# Connectors.net
KiCad netlist of a schematic drawn in Altium Designer
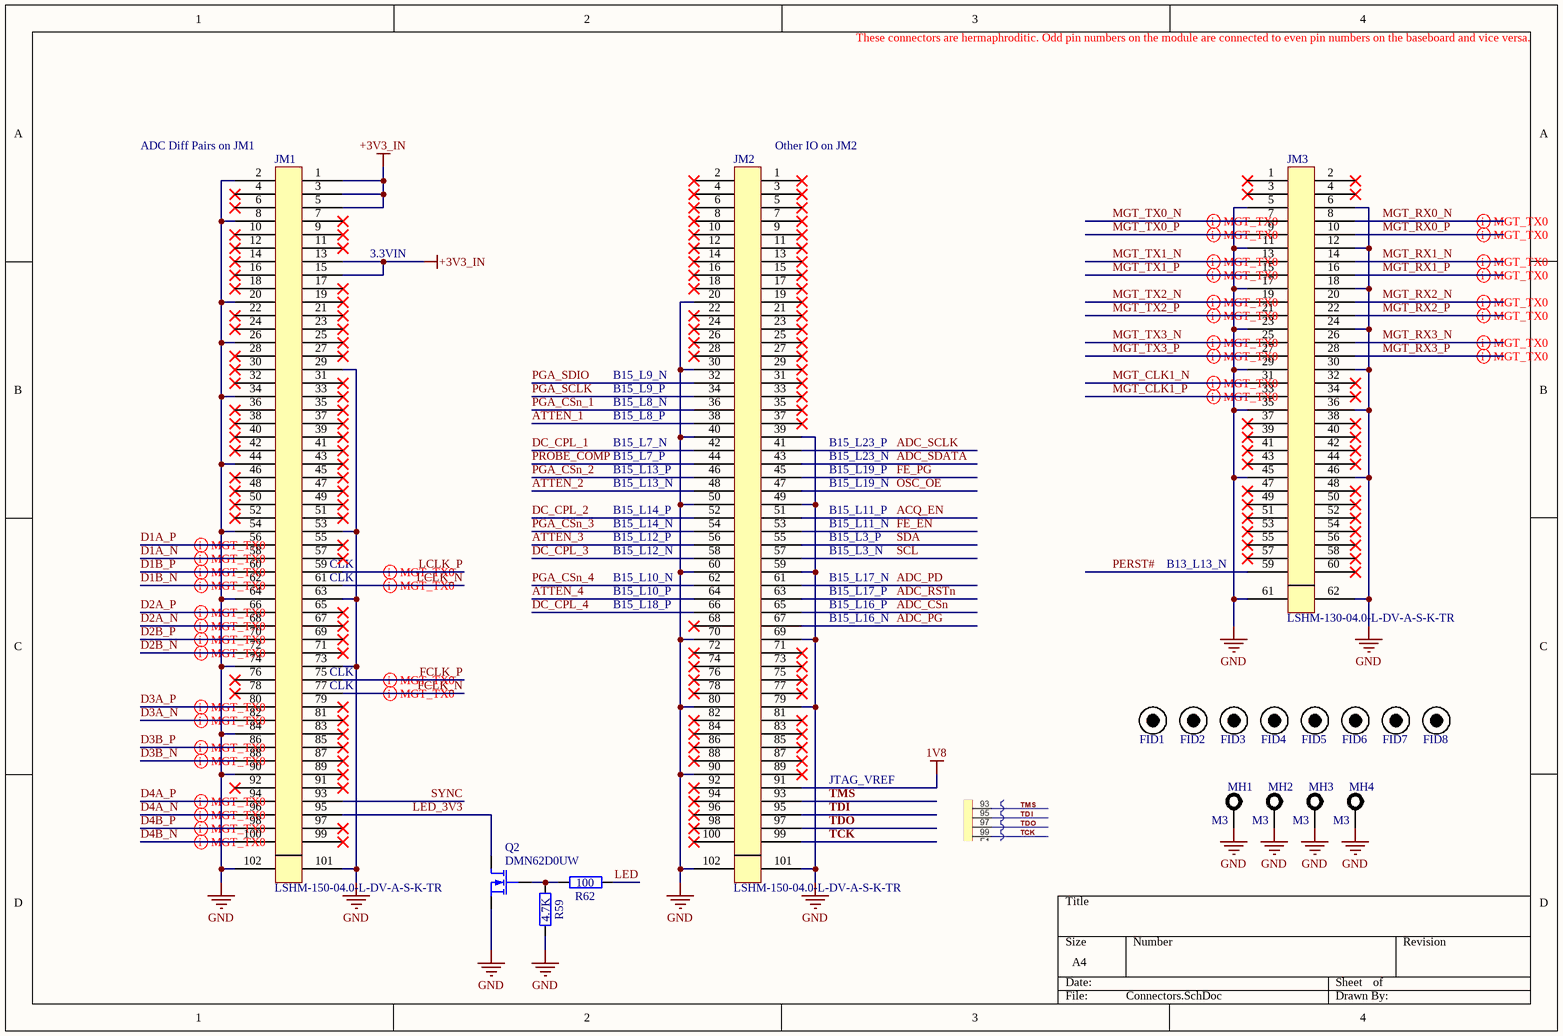
[diagram p0: Connectors.SchDoc]

(export (version "E")
  (design (tool "Eeschema 10.0.6"))
  (components
    (comp (ref "FID1") (value "PCB") (footprint "GEN_FID") (libsource (lib "DSO") (part "FID 1mm")))
    (comp (ref "FID2") (value "PCB") (footprint "GEN_FID") (libsource (lib "DSO") (part "FID 1mm")))
    (comp (ref "FID3") (value "PCB") (footprint "GEN_FID") (libsource (lib "DSO") (part "FID 1mm")))
    (comp (ref "FID4") (value "PCB") (footprint "GEN_FID") (libsource (lib "DSO") (part "FID 1mm")))
    (comp (ref "FID5") (value "PCB") (footprint "GEN_FID") (libsource (lib "DSO") (part "FID 1mm")))
    (comp (ref "FID6") (value "PCB") (footprint "GEN_FID") (libsource (lib "DSO") (part "FID 1mm")))
    (comp (ref "FID7") (value "PCB") (footprint "GEN_FID") (libsource (lib "DSO") (part "FID 1mm")))
    (comp (ref "FID8") (value "PCB") (footprint "GEN_FID") (libsource (lib "DSO") (part "FID 1mm")))
    (comp (ref "JM1")
      (value "LSHM-150-04.0-L-DV-A-S-K-TR")
      (footprint "SAM_LSHM-150-XX.X-XX-DV-A-S")
      (libsource (lib "DSO") (part "CONN LSHM-150-04.0-L-DV-A-S-K-TR"))
    )
    (comp (ref "JM2")
      (value "LSHM-150-04.0-L-DV-A-S-K-TR")
      (footprint "SAM_LSHM-150-XX.X-XX-DV-A-S")
      (libsource (lib "DSO") (part "CONN LSHM-150-04.0-L-DV-A-S-K-TR"))
    )
    (comp (ref "JM3")
      (value "LSHM-130-04.0-L-DV-A-S-K-TR")
      (footprint "SAM_LSHM-130-XX.X-XX-DV-A-S")
      (libsource (lib "DSO") (part "CONN LSHM-130-04.0-L-DV-A-S-K-TR"))
    )
    (comp (ref "MH1") (value "M3") (footprint "MH M3") (libsource (lib "DSO") (part "MH M3")))
    (comp (ref "MH2") (value "M3") (footprint "MH M3") (libsource (lib "DSO") (part "MH M3")))
    (comp (ref "MH3") (value "M3") (footprint "MH M3") (libsource (lib "DSO") (part "MH M3")))
    (comp (ref "MH4") (value "M3") (footprint "MH M3") (libsource (lib "DSO") (part "MH M3")))
    (comp (ref "Q2")
      (value "DMN62D0UW")
      (footprint "GEN_SOT_323")
      (libsource (lib "DSO") (part "NMOS DMN62D0UW"))
    )
    (comp (ref "R59")
      (value "4.7K")
      (footprint "GEN_R_0201")
      (fields (field (name "TOLERANCE") "1%"))
      (libsource (lib "DSO") (part "RES 4.7K OHM 1% 1/20W 0201"))
    )
    (comp (ref "R62")
      (value "100")
      (footprint "GEN_R_0201")
      (fields (field (name "TOLERANCE") "1%"))
      (libsource (lib "DSO") (part "RES 100 OHM 1% 1/20W 0201"))
    )
  )
  (nets
    (net (code "1") (name "+3V3_IN") (class "Default")
      (node (ref "JM1") (pin "1") (pinfunction "1_1") (pintype "passive"))
      (node (ref "JM1") (pin "13") (pinfunction "13_13") (pintype "passive"))
      (node (ref "JM1") (pin "15") (pinfunction "15_15") (pintype "passive"))
      (node (ref "JM1") (pin "3") (pinfunction "3_3") (pintype "passive"))
      (node (ref "JM1") (pin "5") (pinfunction "5_5") (pintype "passive"))
    )
    (net (code "2") (name "/ACQ_EN") (class "Default")
      (node (ref "JM2") (pin "51") (pinfunction "51_51") (pintype "passive"))
    )
    (net (code "3") (name "/ADC_CSn") (class "Default")
      (node (ref "JM2") (pin "65") (pinfunction "65_65") (pintype "passive"))
    )
    (net (code "4") (name "/ADC_PD") (class "Default")
      (node (ref "JM2") (pin "61") (pinfunction "61_61") (pintype "passive"))
    )
    (net (code "5") (name "/ADC_PG") (class "Default")
      (node (ref "JM2") (pin "67") (pinfunction "67_67") (pintype "passive"))
    )
    (net (code "6") (name "/ADC_RSTn") (class "Default")
      (node (ref "JM2") (pin "63") (pinfunction "63_63") (pintype "passive"))
    )
    (net (code "7") (name "/ADC_SCLK") (class "Default")
      (node (ref "JM2") (pin "41") (pinfunction "41_41") (pintype "passive"))
    )
    (net (code "8") (name "/ADC_SDATA") (class "Default")
      (node (ref "JM2") (pin "43") (pinfunction "43_43") (pintype "passive"))
    )
    (net (code "9") (name "/ATTEN_1") (class "Default")
      (node (ref "JM2") (pin "38") (pinfunction "38_38") (pintype "passive"))
    )
    (net (code "10") (name "/ATTEN_2") (class "Default")
      (node (ref "JM2") (pin "48") (pinfunction "48_48") (pintype "passive"))
    )
    (net (code "11") (name "/ATTEN_3") (class "Default")
      (node (ref "JM2") (pin "56") (pinfunction "56_56") (pintype "passive"))
    )
    (net (code "12") (name "/ATTEN_4") (class "Default")
      (node (ref "JM2") (pin "64") (pinfunction "64_64") (pintype "passive"))
    )
    (net (code "13") (name "/D1A_N") (class "Default")
      (node (ref "JM1") (pin "58") (pinfunction "58_58") (pintype "passive"))
    )
    (net (code "14") (name "/D1A_P") (class "Default")
      (node (ref "JM1") (pin "56") (pinfunction "56_56") (pintype "passive"))
    )
    (net (code "15") (name "/D1B_N") (class "Default")
      (node (ref "JM1") (pin "62") (pinfunction "62_62") (pintype "passive"))
    )
    (net (code "16") (name "/D1B_P") (class "Default")
      (node (ref "JM1") (pin "60") (pinfunction "60_60") (pintype "passive"))
    )
    (net (code "17") (name "/D2A_N") (class "Default")
      (node (ref "JM1") (pin "68") (pinfunction "68_68") (pintype "passive"))
    )
    (net (code "18") (name "/D2A_P") (class "Default")
      (node (ref "JM1") (pin "66") (pinfunction "66_66") (pintype "passive"))
    )
    (net (code "19") (name "/D2B_N") (class "Default")
      (node (ref "JM1") (pin "72") (pinfunction "72_72") (pintype "passive"))
    )
    (net (code "20") (name "/D2B_P") (class "Default")
      (node (ref "JM1") (pin "70") (pinfunction "70_70") (pintype "passive"))
    )
    (net (code "21") (name "/D3A_N") (class "Default")
      (node (ref "JM1") (pin "82") (pinfunction "82_82") (pintype "passive"))
    )
    (net (code "22") (name "/D3A_P") (class "Default")
      (node (ref "JM1") (pin "80") (pinfunction "80_80") (pintype "passive"))
    )
    (net (code "23") (name "/D3B_N") (class "Default")
      (node (ref "JM1") (pin "88") (pinfunction "88_88") (pintype "passive"))
    )
    (net (code "24") (name "/D3B_P") (class "Default")
      (node (ref "JM1") (pin "86") (pinfunction "86_86") (pintype "passive"))
    )
    (net (code "25") (name "/D4A_N") (class "Default")
      (node (ref "JM1") (pin "96") (pinfunction "96_96") (pintype "passive"))
    )
    (net (code "26") (name "/D4A_P") (class "Default")
      (node (ref "JM1") (pin "94") (pinfunction "94_94") (pintype "passive"))
    )
    (net (code "27") (name "/D4B_N") (class "Default")
      (node (ref "JM1") (pin "100") (pinfunction "100_100") (pintype "passive"))
    )
    (net (code "28") (name "/D4B_P") (class "Default")
      (node (ref "JM1") (pin "98") (pinfunction "98_98") (pintype "passive"))
    )
    (net (code "29") (name "/DC_CPL_1") (class "Default")
      (node (ref "JM2") (pin "42") (pinfunction "42_42") (pintype "passive"))
    )
    (net (code "30") (name "/DC_CPL_2") (class "Default")
      (node (ref "JM2") (pin "52") (pinfunction "52_52") (pintype "passive"))
    )
    (net (code "31") (name "/DC_CPL_3") (class "Default")
      (node (ref "JM2") (pin "58") (pinfunction "58_58") (pintype "passive"))
    )
    (net (code "32") (name "/DC_CPL_4") (class "Default")
      (node (ref "JM2") (pin "66") (pinfunction "66_66") (pintype "passive"))
    )
    (net (code "33") (name "/FCLK_N") (class "Default")
      (node (ref "JM1") (pin "77") (pinfunction "77_77") (pintype "passive"))
    )
    (net (code "34") (name "/FCLK_P") (class "Default")
      (node (ref "JM1") (pin "75") (pinfunction "75_75") (pintype "passive"))
    )
    (net (code "35") (name "/FE_EN") (class "Default")
      (node (ref "JM2") (pin "53") (pinfunction "53_53") (pintype "passive"))
    )
    (net (code "36") (name "/FE_PG") (class "Default")
      (node (ref "JM2") (pin "45") (pinfunction "45_45") (pintype "passive"))
    )
    (net (code "37") (name "/LCLK_N") (class "Default")
      (node (ref "JM1") (pin "61") (pinfunction "61_61") (pintype "passive"))
    )
    (net (code "38") (name "/LCLK_P") (class "Default")
      (node (ref "JM1") (pin "59") (pinfunction "59_59") (pintype "passive"))
    )
    (net (code "39") (name "/LED") (class "Default")
      (node (ref "R62") (pin "1") (pinfunction "1_1") (pintype "passive"))
    )
    (net (code "40") (name "/LED_3V3") (class "Default")
      (node (ref "JM1") (pin "95") (pinfunction "95_95") (pintype "passive"))
      (node (ref "Q2") (pin "1") (pinfunction "D_1") (pintype "passive"))
    )
    (net (code "41") (name "/MGT_CLK1_N") (class "Default")
      (node (ref "JM3") (pin "31") (pinfunction "31_31") (pintype "passive"))
    )
    (net (code "42") (name "/MGT_CLK1_P") (class "Default")
      (node (ref "JM3") (pin "33") (pinfunction "33_33") (pintype "passive"))
    )
    (net (code "43") (name "/MGT_RX0_N") (class "Default")
      (node (ref "JM3") (pin "8") (pinfunction "8_8") (pintype "passive"))
    )
    (net (code "44") (name "/MGT_RX0_P") (class "Default")
      (node (ref "JM3") (pin "10") (pinfunction "10_10") (pintype "passive"))
    )
    (net (code "45") (name "/MGT_RX1_N") (class "Default")
      (node (ref "JM3") (pin "14") (pinfunction "14_14") (pintype "passive"))
    )
    (net (code "46") (name "/MGT_RX1_P") (class "Default")
      (node (ref "JM3") (pin "16") (pinfunction "16_16") (pintype "passive"))
    )
    (net (code "47") (name "/MGT_RX2_N") (class "Default")
      (node (ref "JM3") (pin "20") (pinfunction "20_20") (pintype "passive"))
    )
    (net (code "48") (name "/MGT_RX2_P") (class "Default")
      (node (ref "JM3") (pin "22") (pinfunction "22_22") (pintype "passive"))
    )
    (net (code "49") (name "/MGT_RX3_N") (class "Default")
      (node (ref "JM3") (pin "26") (pinfunction "26_26") (pintype "passive"))
    )
    (net (code "50") (name "/MGT_RX3_P") (class "Default")
      (node (ref "JM3") (pin "28") (pinfunction "28_28") (pintype "passive"))
    )
    (net (code "51") (name "/MGT_TX0_N") (class "Default")
      (node (ref "JM3") (pin "7") (pinfunction "7_7") (pintype "passive"))
    )
    (net (code "52") (name "/MGT_TX0_P") (class "Default")
      (node (ref "JM3") (pin "9") (pinfunction "9_9") (pintype "passive"))
    )
    (net (code "53") (name "/MGT_TX1_N") (class "Default")
      (node (ref "JM3") (pin "13") (pinfunction "13_13") (pintype "passive"))
    )
    (net (code "54") (name "/MGT_TX1_P") (class "Default")
      (node (ref "JM3") (pin "15") (pinfunction "15_15") (pintype "passive"))
    )
    (net (code "55") (name "/MGT_TX2_N") (class "Default")
      (node (ref "JM3") (pin "19") (pinfunction "19_19") (pintype "passive"))
    )
    (net (code "56") (name "/MGT_TX2_P") (class "Default")
      (node (ref "JM3") (pin "21") (pinfunction "21_21") (pintype "passive"))
    )
    (net (code "57") (name "/MGT_TX3_N") (class "Default")
      (node (ref "JM3") (pin "25") (pinfunction "25_25") (pintype "passive"))
    )
    (net (code "58") (name "/MGT_TX3_P") (class "Default")
      (node (ref "JM3") (pin "27") (pinfunction "27_27") (pintype "passive"))
    )
    (net (code "59") (name "/OSC_OE") (class "Default")
      (node (ref "JM2") (pin "47") (pinfunction "47_47") (pintype "passive"))
    )
    (net (code "60") (name "/PERST#") (class "Default")
      (node (ref "JM3") (pin "59") (pinfunction "59_59") (pintype "passive"))
    )
    (net (code "61") (name "/PGA_CSn_1") (class "Default")
      (node (ref "JM2") (pin "36") (pinfunction "36_36") (pintype "passive"))
    )
    (net (code "62") (name "/PGA_CSn_2") (class "Default")
      (node (ref "JM2") (pin "46") (pinfunction "46_46") (pintype "passive"))
    )
    (net (code "63") (name "/PGA_CSn_3") (class "Default")
      (node (ref "JM2") (pin "54") (pinfunction "54_54") (pintype "passive"))
    )
    (net (code "64") (name "/PGA_CSn_4") (class "Default")
      (node (ref "JM2") (pin "62") (pinfunction "62_62") (pintype "passive"))
    )
    (net (code "65") (name "/PGA_SCLK") (class "Default")
      (node (ref "JM2") (pin "34") (pinfunction "34_34") (pintype "passive"))
    )
    (net (code "66") (name "/PGA_SDIO") (class "Default")
      (node (ref "JM2") (pin "32") (pinfunction "32_32") (pintype "passive"))
    )
    (net (code "67") (name "/PROBE_COMP") (class "Default")
      (node (ref "JM2") (pin "44") (pinfunction "44_44") (pintype "passive"))
    )
    (net (code "68") (name "/SCL") (class "Default")
      (node (ref "JM2") (pin "57") (pinfunction "57_57") (pintype "passive"))
    )
    (net (code "69") (name "/SDA") (class "Default")
      (node (ref "JM2") (pin "55") (pinfunction "55_55") (pintype "passive"))
    )
    (net (code "70") (name "/SYNC") (class "Default")
      (node (ref "JM1") (pin "93") (pinfunction "93_93") (pintype "passive"))
    )
    (net (code "71") (name "/TCK") (class "Default")
      (node (ref "JM2") (pin "99") (pinfunction "99_99") (pintype "passive"))
    )
    (net (code "72") (name "/TDI") (class "Default")
      (node (ref "JM2") (pin "95") (pinfunction "95_95") (pintype "passive"))
    )
    (net (code "73") (name "/TDO") (class "Default")
      (node (ref "JM2") (pin "97") (pinfunction "97_97") (pintype "passive"))
    )
    (net (code "74") (name "/TMS") (class "Default")
      (node (ref "JM2") (pin "93") (pinfunction "93_93") (pintype "passive"))
    )
    (net (code "75") (name "1V8") (class "Default")
      (node (ref "JM2") (pin "91") (pinfunction "91_91") (pintype "passive"))
    )
    (net (code "76") (name "GND") (class "Default")
      (node (ref "JM1") (pin "101") (pinfunction "101_101") (pintype "passive"))
      (node (ref "JM1") (pin "102") (pinfunction "102_102") (pintype "passive"))
      (node (ref "JM1") (pin "2") (pinfunction "2_2") (pintype "passive"))
      (node (ref "JM1") (pin "20") (pinfunction "20_20") (pintype "passive"))
      (node (ref "JM1") (pin "26") (pinfunction "26_26") (pintype "passive"))
      (node (ref "JM1") (pin "29") (pinfunction "29_29") (pintype "passive"))
      (node (ref "JM1") (pin "34") (pinfunction "34_34") (pintype "passive"))
      (node (ref "JM1") (pin "44") (pinfunction "44_44") (pintype "passive"))
      (node (ref "JM1") (pin "53") (pinfunction "53_53") (pintype "passive"))
      (node (ref "JM1") (pin "54") (pinfunction "54_54") (pintype "passive"))
      (node (ref "JM1") (pin "63") (pinfunction "63_63") (pintype "passive"))
      (node (ref "JM1") (pin "64") (pinfunction "64_64") (pintype "passive"))
      (node (ref "JM1") (pin "73") (pinfunction "73_73") (pintype "passive"))
      (node (ref "JM1") (pin "74") (pinfunction "74_74") (pintype "passive"))
      (node (ref "JM1") (pin "8") (pinfunction "8_8") (pintype "passive"))
      (node (ref "JM1") (pin "84") (pinfunction "84_84") (pintype "passive"))
      (node (ref "JM1") (pin "90") (pinfunction "90_90") (pintype "passive"))
      (node (ref "JM2") (pin "101") (pinfunction "101_101") (pintype "passive"))
      (node (ref "JM2") (pin "102") (pinfunction "102_102") (pintype "passive"))
      (node (ref "JM2") (pin "20") (pinfunction "20_20") (pintype "passive"))
      (node (ref "JM2") (pin "30") (pinfunction "30_30") (pintype "passive"))
      (node (ref "JM2") (pin "39") (pinfunction "39_39") (pintype "passive"))
      (node (ref "JM2") (pin "40") (pinfunction "40_40") (pintype "passive"))
      (node (ref "JM2") (pin "49") (pinfunction "49_49") (pintype "passive"))
      (node (ref "JM2") (pin "50") (pinfunction "50_50") (pintype "passive"))
      (node (ref "JM2") (pin "59") (pinfunction "59_59") (pintype "passive"))
      (node (ref "JM2") (pin "60") (pinfunction "60_60") (pintype "passive"))
      (node (ref "JM2") (pin "69") (pinfunction "69_69") (pintype "passive"))
      (node (ref "JM2") (pin "70") (pinfunction "70_70") (pintype "passive"))
      (node (ref "JM2") (pin "79") (pinfunction "79_79") (pintype "passive"))
      (node (ref "JM2") (pin "80") (pinfunction "80_80") (pintype "passive"))
      (node (ref "JM2") (pin "90") (pinfunction "90_90") (pintype "passive"))
      (node (ref "JM3") (pin "11") (pinfunction "11_11") (pintype "passive"))
      (node (ref "JM3") (pin "12") (pinfunction "12_12") (pintype "passive"))
      (node (ref "JM3") (pin "17") (pinfunction "17_17") (pintype "passive"))
      (node (ref "JM3") (pin "18") (pinfunction "18_18") (pintype "passive"))
      (node (ref "JM3") (pin "23") (pinfunction "23_23") (pintype "passive"))
      (node (ref "JM3") (pin "24") (pinfunction "24_24") (pintype "passive"))
      (node (ref "JM3") (pin "29") (pinfunction "29_29") (pintype "passive"))
      (node (ref "JM3") (pin "30") (pinfunction "30_30") (pintype "passive"))
      (node (ref "JM3") (pin "35") (pinfunction "35_35") (pintype "passive"))
      (node (ref "JM3") (pin "36") (pinfunction "36_36") (pintype "passive"))
      (node (ref "JM3") (pin "45") (pinfunction "45_45") (pintype "passive"))
      (node (ref "JM3") (pin "46") (pinfunction "46_46") (pintype "passive"))
      (node (ref "JM3") (pin "5") (pinfunction "5_5") (pintype "passive"))
      (node (ref "JM3") (pin "6") (pinfunction "6_6") (pintype "passive"))
      (node (ref "JM3") (pin "61") (pinfunction "61_61") (pintype "passive"))
      (node (ref "JM3") (pin "62") (pinfunction "62_62") (pintype "passive"))
      (node (ref "MH1") (pin "1") (pinfunction "1_1") (pintype "passive"))
      (node (ref "MH2") (pin "1") (pinfunction "1_1") (pintype "passive"))
      (node (ref "MH3") (pin "1") (pinfunction "1_1") (pintype "passive"))
      (node (ref "MH4") (pin "1") (pinfunction "1_1") (pintype "passive"))
      (node (ref "Q2") (pin "3") (pinfunction "S_3") (pintype "passive"))
      (node (ref "R59") (pin "2") (pinfunction "2_2") (pintype "passive"))
    )
    (net (code "77") (name "Net-(Q2-G)") (class "Default")
      (node (ref "Q2") (pin "2") (pinfunction "G_2") (pintype "passive"))
      (node (ref "R59") (pin "1") (pinfunction "1_1") (pintype "passive"))
      (node (ref "R62") (pin "2") (pinfunction "2_2") (pintype "passive"))
    )
    (net (code "78") (name "unconnected-(JM1-Pad4)") (class "Default")
      (node (ref "JM1") (pin "4") (pinfunction "4_4") (pintype "passive+no_connect"))
    )
    (net (code "79") (name "unconnected-(JM1-Pad6)") (class "Default")
      (node (ref "JM1") (pin "6") (pinfunction "6_6") (pintype "passive+no_connect"))
    )
    (net (code "80") (name "unconnected-(JM1-Pad7)") (class "Default")
      (node (ref "JM1") (pin "7") (pinfunction "7_7") (pintype "passive+no_connect"))
    )
    (net (code "81") (name "unconnected-(JM1-Pad9)") (class "Default")
      (node (ref "JM1") (pin "9") (pinfunction "9_9") (pintype "passive+no_connect"))
    )
    (net (code "82") (name "unconnected-(JM1-Pad10)") (class "Default")
      (node (ref "JM1") (pin "10") (pinfunction "10_10") (pintype "passive+no_connect"))
    )
    (net (code "83") (name "unconnected-(JM1-Pad11)") (class "Default")
      (node (ref "JM1") (pin "11") (pinfunction "11_11") (pintype "passive+no_connect"))
    )
    (net (code "84") (name "unconnected-(JM1-Pad12)") (class "Default")
      (node (ref "JM1") (pin "12") (pinfunction "12_12") (pintype "passive+no_connect"))
    )
    (net (code "85") (name "unconnected-(JM1-Pad14)") (class "Default")
      (node (ref "JM1") (pin "14") (pinfunction "14_14") (pintype "passive+no_connect"))
    )
    (net (code "86") (name "unconnected-(JM1-Pad16)") (class "Default")
      (node (ref "JM1") (pin "16") (pinfunction "16_16") (pintype "passive+no_connect"))
    )
    (net (code "87") (name "unconnected-(JM1-Pad17)") (class "Default")
      (node (ref "JM1") (pin "17") (pinfunction "17_17") (pintype "passive+no_connect"))
    )
    (net (code "88") (name "unconnected-(JM1-Pad18)") (class "Default")
      (node (ref "JM1") (pin "18") (pinfunction "18_18") (pintype "passive+no_connect"))
    )
    (net (code "89") (name "unconnected-(JM1-Pad19)") (class "Default")
      (node (ref "JM1") (pin "19") (pinfunction "19_19") (pintype "passive+no_connect"))
    )
    (net (code "90") (name "unconnected-(JM1-Pad21)") (class "Default")
      (node (ref "JM1") (pin "21") (pinfunction "21_21") (pintype "passive+no_connect"))
    )
    (net (code "91") (name "unconnected-(JM1-Pad22)") (class "Default")
      (node (ref "JM1") (pin "22") (pinfunction "22_22") (pintype "passive+no_connect"))
    )
    (net (code "92") (name "unconnected-(JM1-Pad23)") (class "Default")
      (node (ref "JM1") (pin "23") (pinfunction "23_23") (pintype "passive+no_connect"))
    )
    (net (code "93") (name "unconnected-(JM1-Pad24)") (class "Default")
      (node (ref "JM1") (pin "24") (pinfunction "24_24") (pintype "passive+no_connect"))
    )
    (net (code "94") (name "unconnected-(JM1-Pad25)") (class "Default")
      (node (ref "JM1") (pin "25") (pinfunction "25_25") (pintype "passive+no_connect"))
    )
    (net (code "95") (name "unconnected-(JM1-Pad27)") (class "Default")
      (node (ref "JM1") (pin "27") (pinfunction "27_27") (pintype "passive+no_connect"))
    )
    (net (code "96") (name "unconnected-(JM1-Pad28)") (class "Default")
      (node (ref "JM1") (pin "28") (pinfunction "28_28") (pintype "passive+no_connect"))
    )
    (net (code "97") (name "unconnected-(JM1-Pad30)") (class "Default")
      (node (ref "JM1") (pin "30") (pinfunction "30_30") (pintype "passive+no_connect"))
    )
    (net (code "98") (name "unconnected-(JM1-Pad31)") (class "Default")
      (node (ref "JM1") (pin "31") (pinfunction "31_31") (pintype "passive+no_connect"))
    )
    (net (code "99") (name "unconnected-(JM1-Pad32)") (class "Default")
      (node (ref "JM1") (pin "32") (pinfunction "32_32") (pintype "passive+no_connect"))
    )
    (net (code "100") (name "unconnected-(JM1-Pad33)") (class "Default")
      (node (ref "JM1") (pin "33") (pinfunction "33_33") (pintype "passive+no_connect"))
    )
    (net (code "101") (name "unconnected-(JM1-Pad35)") (class "Default")
      (node (ref "JM1") (pin "35") (pinfunction "35_35") (pintype "passive+no_connect"))
    )
    (net (code "102") (name "unconnected-(JM1-Pad36)") (class "Default")
      (node (ref "JM1") (pin "36") (pinfunction "36_36") (pintype "passive+no_connect"))
    )
    (net (code "103") (name "unconnected-(JM1-Pad37)") (class "Default")
      (node (ref "JM1") (pin "37") (pinfunction "37_37") (pintype "passive+no_connect"))
    )
    (net (code "104") (name "unconnected-(JM1-Pad38)") (class "Default")
      (node (ref "JM1") (pin "38") (pinfunction "38_38") (pintype "passive+no_connect"))
    )
    (net (code "105") (name "unconnected-(JM1-Pad39)") (class "Default")
      (node (ref "JM1") (pin "39") (pinfunction "39_39") (pintype "passive+no_connect"))
    )
    (net (code "106") (name "unconnected-(JM1-Pad40)") (class "Default")
      (node (ref "JM1") (pin "40") (pinfunction "40_40") (pintype "passive+no_connect"))
    )
    (net (code "107") (name "unconnected-(JM1-Pad41)") (class "Default")
      (node (ref "JM1") (pin "41") (pinfunction "41_41") (pintype "passive+no_connect"))
    )
    (net (code "108") (name "unconnected-(JM1-Pad42)") (class "Default")
      (node (ref "JM1") (pin "42") (pinfunction "42_42") (pintype "passive+no_connect"))
    )
    (net (code "109") (name "unconnected-(JM1-Pad43)") (class "Default")
      (node (ref "JM1") (pin "43") (pinfunction "43_43") (pintype "passive+no_connect"))
    )
    (net (code "110") (name "unconnected-(JM1-Pad45)") (class "Default")
      (node (ref "JM1") (pin "45") (pinfunction "45_45") (pintype "passive+no_connect"))
    )
    (net (code "111") (name "unconnected-(JM1-Pad46)") (class "Default")
      (node (ref "JM1") (pin "46") (pinfunction "46_46") (pintype "passive+no_connect"))
    )
    (net (code "112") (name "unconnected-(JM1-Pad47)") (class "Default")
      (node (ref "JM1") (pin "47") (pinfunction "47_47") (pintype "passive+no_connect"))
    )
    (net (code "113") (name "unconnected-(JM1-Pad48)") (class "Default")
      (node (ref "JM1") (pin "48") (pinfunction "48_48") (pintype "passive+no_connect"))
    )
    (net (code "114") (name "unconnected-(JM1-Pad49)") (class "Default")
      (node (ref "JM1") (pin "49") (pinfunction "49_49") (pintype "passive+no_connect"))
    )
    (net (code "115") (name "unconnected-(JM1-Pad50)") (class "Default")
      (node (ref "JM1") (pin "50") (pinfunction "50_50") (pintype "passive+no_connect"))
    )
    (net (code "116") (name "unconnected-(JM1-Pad51)") (class "Default")
      (node (ref "JM1") (pin "51") (pinfunction "51_51") (pintype "passive+no_connect"))
    )
    (net (code "117") (name "unconnected-(JM1-Pad52)") (class "Default")
      (node (ref "JM1") (pin "52") (pinfunction "52_52") (pintype "passive+no_connect"))
    )
    (net (code "118") (name "unconnected-(JM1-Pad55)") (class "Default")
      (node (ref "JM1") (pin "55") (pinfunction "55_55") (pintype "passive+no_connect"))
    )
    (net (code "119") (name "unconnected-(JM1-Pad57)") (class "Default")
      (node (ref "JM1") (pin "57") (pinfunction "57_57") (pintype "passive+no_connect"))
    )
    (net (code "120") (name "unconnected-(JM1-Pad65)") (class "Default")
      (node (ref "JM1") (pin "65") (pinfunction "65_65") (pintype "passive+no_connect"))
    )
    (net (code "121") (name "unconnected-(JM1-Pad67)") (class "Default")
      (node (ref "JM1") (pin "67") (pinfunction "67_67") (pintype "passive+no_connect"))
    )
    (net (code "122") (name "unconnected-(JM1-Pad69)") (class "Default")
      (node (ref "JM1") (pin "69") (pinfunction "69_69") (pintype "passive+no_connect"))
    )
    (net (code "123") (name "unconnected-(JM1-Pad71)") (class "Default")
      (node (ref "JM1") (pin "71") (pinfunction "71_71") (pintype "passive+no_connect"))
    )
    (net (code "124") (name "unconnected-(JM1-Pad76)") (class "Default")
      (node (ref "JM1") (pin "76") (pinfunction "76_76") (pintype "passive+no_connect"))
    )
    (net (code "125") (name "unconnected-(JM1-Pad78)") (class "Default")
      (node (ref "JM1") (pin "78") (pinfunction "78_78") (pintype "passive+no_connect"))
    )
    (net (code "126") (name "unconnected-(JM1-Pad79)") (class "Default")
      (node (ref "JM1") (pin "79") (pinfunction "79_79") (pintype "passive+no_connect"))
    )
    (net (code "127") (name "unconnected-(JM1-Pad81)") (class "Default")
      (node (ref "JM1") (pin "81") (pinfunction "81_81") (pintype "passive+no_connect"))
    )
    (net (code "128") (name "unconnected-(JM1-Pad83)") (class "Default")
      (node (ref "JM1") (pin "83") (pinfunction "83_83") (pintype "passive+no_connect"))
    )
    (net (code "129") (name "unconnected-(JM1-Pad85)") (class "Default")
      (node (ref "JM1") (pin "85") (pinfunction "85_85") (pintype "passive+no_connect"))
    )
    (net (code "130") (name "unconnected-(JM1-Pad87)") (class "Default")
      (node (ref "JM1") (pin "87") (pinfunction "87_87") (pintype "passive+no_connect"))
    )
    (net (code "131") (name "unconnected-(JM1-Pad89)") (class "Default")
      (node (ref "JM1") (pin "89") (pinfunction "89_89") (pintype "passive+no_connect"))
    )
    (net (code "132") (name "unconnected-(JM1-Pad91)") (class "Default")
      (node (ref "JM1") (pin "91") (pinfunction "91_91") (pintype "passive+no_connect"))
    )
    (net (code "133") (name "unconnected-(JM1-Pad92)") (class "Default")
      (node (ref "JM1") (pin "92") (pinfunction "92_92") (pintype "passive+no_connect"))
    )
    (net (code "134") (name "unconnected-(JM1-Pad97)") (class "Default")
      (node (ref "JM1") (pin "97") (pinfunction "97_97") (pintype "passive+no_connect"))
    )
    (net (code "135") (name "unconnected-(JM1-Pad99)") (class "Default")
      (node (ref "JM1") (pin "99") (pinfunction "99_99") (pintype "passive+no_connect"))
    )
    (net (code "136") (name "unconnected-(JM2-Pad1)") (class "Default")
      (node (ref "JM2") (pin "1") (pinfunction "1_1") (pintype "passive+no_connect"))
    )
    (net (code "137") (name "unconnected-(JM2-Pad2)") (class "Default")
      (node (ref "JM2") (pin "2") (pinfunction "2_2") (pintype "passive+no_connect"))
    )
    (net (code "138") (name "unconnected-(JM2-Pad3)") (class "Default")
      (node (ref "JM2") (pin "3") (pinfunction "3_3") (pintype "passive+no_connect"))
    )
    (net (code "139") (name "unconnected-(JM2-Pad4)") (class "Default")
      (node (ref "JM2") (pin "4") (pinfunction "4_4") (pintype "passive+no_connect"))
    )
    (net (code "140") (name "unconnected-(JM2-Pad5)") (class "Default")
      (node (ref "JM2") (pin "5") (pinfunction "5_5") (pintype "passive+no_connect"))
    )
    (net (code "141") (name "unconnected-(JM2-Pad6)") (class "Default")
      (node (ref "JM2") (pin "6") (pinfunction "6_6") (pintype "passive+no_connect"))
    )
    (net (code "142") (name "unconnected-(JM2-Pad7)") (class "Default")
      (node (ref "JM2") (pin "7") (pinfunction "7_7") (pintype "passive+no_connect"))
    )
    (net (code "143") (name "unconnected-(JM2-Pad8)") (class "Default")
      (node (ref "JM2") (pin "8") (pinfunction "8_8") (pintype "passive+no_connect"))
    )
    (net (code "144") (name "unconnected-(JM2-Pad9)") (class "Default")
      (node (ref "JM2") (pin "9") (pinfunction "9_9") (pintype "passive+no_connect"))
    )
    (net (code "145") (name "unconnected-(JM2-Pad10)") (class "Default")
      (node (ref "JM2") (pin "10") (pinfunction "10_10") (pintype "passive+no_connect"))
    )
    (net (code "146") (name "unconnected-(JM2-Pad11)") (class "Default")
      (node (ref "JM2") (pin "11") (pinfunction "11_11") (pintype "passive+no_connect"))
    )
    (net (code "147") (name "unconnected-(JM2-Pad12)") (class "Default")
      (node (ref "JM2") (pin "12") (pinfunction "12_12") (pintype "passive+no_connect"))
    )
    (net (code "148") (name "unconnected-(JM2-Pad13)") (class "Default")
      (node (ref "JM2") (pin "13") (pinfunction "13_13") (pintype "passive+no_connect"))
    )
    (net (code "149") (name "unconnected-(JM2-Pad14)") (class "Default")
      (node (ref "JM2") (pin "14") (pinfunction "14_14") (pintype "passive+no_connect"))
    )
    (net (code "150") (name "unconnected-(JM2-Pad15)") (class "Default")
      (node (ref "JM2") (pin "15") (pinfunction "15_15") (pintype "passive+no_connect"))
    )
    (net (code "151") (name "unconnected-(JM2-Pad16)") (class "Default")
      (node (ref "JM2") (pin "16") (pinfunction "16_16") (pintype "passive+no_connect"))
    )
    (net (code "152") (name "unconnected-(JM2-Pad17)") (class "Default")
      (node (ref "JM2") (pin "17") (pinfunction "17_17") (pintype "passive+no_connect"))
    )
    (net (code "153") (name "unconnected-(JM2-Pad18)") (class "Default")
      (node (ref "JM2") (pin "18") (pinfunction "18_18") (pintype "passive+no_connect"))
    )
    (net (code "154") (name "unconnected-(JM2-Pad19)") (class "Default")
      (node (ref "JM2") (pin "19") (pinfunction "19_19") (pintype "passive+no_connect"))
    )
    (net (code "155") (name "unconnected-(JM2-Pad21)") (class "Default")
      (node (ref "JM2") (pin "21") (pinfunction "21_21") (pintype "passive+no_connect"))
    )
    (net (code "156") (name "unconnected-(JM2-Pad22)") (class "Default")
      (node (ref "JM2") (pin "22") (pinfunction "22_22") (pintype "passive+no_connect"))
    )
    (net (code "157") (name "unconnected-(JM2-Pad23)") (class "Default")
      (node (ref "JM2") (pin "23") (pinfunction "23_23") (pintype "passive+no_connect"))
    )
    (net (code "158") (name "unconnected-(JM2-Pad24)") (class "Default")
      (node (ref "JM2") (pin "24") (pinfunction "24_24") (pintype "passive+no_connect"))
    )
    (net (code "159") (name "unconnected-(JM2-Pad25)") (class "Default")
      (node (ref "JM2") (pin "25") (pinfunction "25_25") (pintype "passive+no_connect"))
    )
    (net (code "160") (name "unconnected-(JM2-Pad26)") (class "Default")
      (node (ref "JM2") (pin "26") (pinfunction "26_26") (pintype "passive+no_connect"))
    )
    (net (code "161") (name "unconnected-(JM2-Pad27)") (class "Default")
      (node (ref "JM2") (pin "27") (pinfunction "27_27") (pintype "passive+no_connect"))
    )
    (net (code "162") (name "unconnected-(JM2-Pad28)") (class "Default")
      (node (ref "JM2") (pin "28") (pinfunction "28_28") (pintype "passive+no_connect"))
    )
    (net (code "163") (name "unconnected-(JM2-Pad29)") (class "Default")
      (node (ref "JM2") (pin "29") (pinfunction "29_29") (pintype "passive+no_connect"))
    )
    (net (code "164") (name "unconnected-(JM2-Pad31)") (class "Default")
      (node (ref "JM2") (pin "31") (pinfunction "31_31") (pintype "passive+no_connect"))
    )
    (net (code "165") (name "unconnected-(JM2-Pad33)") (class "Default")
      (node (ref "JM2") (pin "33") (pinfunction "33_33") (pintype "passive+no_connect"))
    )
    (net (code "166") (name "unconnected-(JM2-Pad35)") (class "Default")
      (node (ref "JM2") (pin "35") (pinfunction "35_35") (pintype "passive+no_connect"))
    )
    (net (code "167") (name "unconnected-(JM2-Pad37)") (class "Default")
      (node (ref "JM2") (pin "37") (pinfunction "37_37") (pintype "passive+no_connect"))
    )
    (net (code "168") (name "unconnected-(JM2-Pad68)") (class "Default")
      (node (ref "JM2") (pin "68") (pinfunction "68_68") (pintype "passive+no_connect"))
    )
    (net (code "169") (name "unconnected-(JM2-Pad71)") (class "Default")
      (node (ref "JM2") (pin "71") (pinfunction "71_71") (pintype "passive+no_connect"))
    )
    (net (code "170") (name "unconnected-(JM2-Pad72)") (class "Default")
      (node (ref "JM2") (pin "72") (pinfunction "72_72") (pintype "passive+no_connect"))
    )
    (net (code "171") (name "unconnected-(JM2-Pad73)") (class "Default")
      (node (ref "JM2") (pin "73") (pinfunction "73_73") (pintype "passive+no_connect"))
    )
    (net (code "172") (name "unconnected-(JM2-Pad74)") (class "Default")
      (node (ref "JM2") (pin "74") (pinfunction "74_74") (pintype "passive+no_connect"))
    )
    (net (code "173") (name "unconnected-(JM2-Pad75)") (class "Default")
      (node (ref "JM2") (pin "75") (pinfunction "75_75") (pintype "passive+no_connect"))
    )
    (net (code "174") (name "unconnected-(JM2-Pad76)") (class "Default")
      (node (ref "JM2") (pin "76") (pinfunction "76_76") (pintype "passive+no_connect"))
    )
    (net (code "175") (name "unconnected-(JM2-Pad77)") (class "Default")
      (node (ref "JM2") (pin "77") (pinfunction "77_77") (pintype "passive+no_connect"))
    )
    (net (code "176") (name "unconnected-(JM2-Pad78)") (class "Default")
      (node (ref "JM2") (pin "78") (pinfunction "78_78") (pintype "passive+no_connect"))
    )
    (net (code "177") (name "unconnected-(JM2-Pad81)") (class "Default")
      (node (ref "JM2") (pin "81") (pinfunction "81_81") (pintype "passive+no_connect"))
    )
    (net (code "178") (name "unconnected-(JM2-Pad82)") (class "Default")
      (node (ref "JM2") (pin "82") (pinfunction "82_82") (pintype "passive+no_connect"))
    )
    (net (code "179") (name "unconnected-(JM2-Pad83)") (class "Default")
      (node (ref "JM2") (pin "83") (pinfunction "83_83") (pintype "passive+no_connect"))
    )
    (net (code "180") (name "unconnected-(JM2-Pad84)") (class "Default")
      (node (ref "JM2") (pin "84") (pinfunction "84_84") (pintype "passive+no_connect"))
    )
    (net (code "181") (name "unconnected-(JM2-Pad85)") (class "Default")
      (node (ref "JM2") (pin "85") (pinfunction "85_85") (pintype "passive+no_connect"))
    )
    (net (code "182") (name "unconnected-(JM2-Pad86)") (class "Default")
      (node (ref "JM2") (pin "86") (pinfunction "86_86") (pintype "passive+no_connect"))
    )
    (net (code "183") (name "unconnected-(JM2-Pad87)") (class "Default")
      (node (ref "JM2") (pin "87") (pinfunction "87_87") (pintype "passive+no_connect"))
    )
    (net (code "184") (name "unconnected-(JM2-Pad88)") (class "Default")
      (node (ref "JM2") (pin "88") (pinfunction "88_88") (pintype "passive+no_connect"))
    )
    (net (code "185") (name "unconnected-(JM2-Pad89)") (class "Default")
      (node (ref "JM2") (pin "89") (pinfunction "89_89") (pintype "passive+no_connect"))
    )
    (net (code "186") (name "unconnected-(JM2-Pad92)") (class "Default")
      (node (ref "JM2") (pin "92") (pinfunction "92_92") (pintype "passive+no_connect"))
    )
    (net (code "187") (name "unconnected-(JM2-Pad94)") (class "Default")
      (node (ref "JM2") (pin "94") (pinfunction "94_94") (pintype "passive+no_connect"))
    )
    (net (code "188") (name "unconnected-(JM2-Pad96)") (class "Default")
      (node (ref "JM2") (pin "96") (pinfunction "96_96") (pintype "passive+no_connect"))
    )
    (net (code "189") (name "unconnected-(JM2-Pad98)") (class "Default")
      (node (ref "JM2") (pin "98") (pinfunction "98_98") (pintype "passive+no_connect"))
    )
    (net (code "190") (name "unconnected-(JM2-Pad100)") (class "Default")
      (node (ref "JM2") (pin "100") (pinfunction "100_100") (pintype "passive+no_connect"))
    )
    (net (code "191") (name "unconnected-(JM3-Pad1)") (class "Default")
      (node (ref "JM3") (pin "1") (pinfunction "1_1") (pintype "passive+no_connect"))
    )
    (net (code "192") (name "unconnected-(JM3-Pad2)") (class "Default")
      (node (ref "JM3") (pin "2") (pinfunction "2_2") (pintype "passive+no_connect"))
    )
    (net (code "193") (name "unconnected-(JM3-Pad3)") (class "Default")
      (node (ref "JM3") (pin "3") (pinfunction "3_3") (pintype "passive+no_connect"))
    )
    (net (code "194") (name "unconnected-(JM3-Pad4)") (class "Default")
      (node (ref "JM3") (pin "4") (pinfunction "4_4") (pintype "passive+no_connect"))
    )
    (net (code "195") (name "unconnected-(JM3-Pad32)") (class "Default")
      (node (ref "JM3") (pin "32") (pinfunction "32_32") (pintype "passive+no_connect"))
    )
    (net (code "196") (name "unconnected-(JM3-Pad34)") (class "Default")
      (node (ref "JM3") (pin "34") (pinfunction "34_34") (pintype "passive+no_connect"))
    )
    (net (code "197") (name "unconnected-(JM3-Pad37)") (class "Default")
      (node (ref "JM3") (pin "37") (pinfunction "37_37") (pintype "passive+no_connect"))
    )
    (net (code "198") (name "unconnected-(JM3-Pad38)") (class "Default")
      (node (ref "JM3") (pin "38") (pinfunction "38_38") (pintype "passive+no_connect"))
    )
    (net (code "199") (name "unconnected-(JM3-Pad39)") (class "Default")
      (node (ref "JM3") (pin "39") (pinfunction "39_39") (pintype "passive+no_connect"))
    )
    (net (code "200") (name "unconnected-(JM3-Pad40)") (class "Default")
      (node (ref "JM3") (pin "40") (pinfunction "40_40") (pintype "passive+no_connect"))
    )
    (net (code "201") (name "unconnected-(JM3-Pad41)") (class "Default")
      (node (ref "JM3") (pin "41") (pinfunction "41_41") (pintype "passive+no_connect"))
    )
    (net (code "202") (name "unconnected-(JM3-Pad42)") (class "Default")
      (node (ref "JM3") (pin "42") (pinfunction "42_42") (pintype "passive+no_connect"))
    )
    (net (code "203") (name "unconnected-(JM3-Pad43)") (class "Default")
      (node (ref "JM3") (pin "43") (pinfunction "43_43") (pintype "passive+no_connect"))
    )
    (net (code "204") (name "unconnected-(JM3-Pad44)") (class "Default")
      (node (ref "JM3") (pin "44") (pinfunction "44_44") (pintype "passive+no_connect"))
    )
    (net (code "205") (name "unconnected-(JM3-Pad47)") (class "Default")
      (node (ref "JM3") (pin "47") (pinfunction "47_47") (pintype "passive+no_connect"))
    )
    (net (code "206") (name "unconnected-(JM3-Pad48)") (class "Default")
      (node (ref "JM3") (pin "48") (pinfunction "48_48") (pintype "passive+no_connect"))
    )
    (net (code "207") (name "unconnected-(JM3-Pad49)") (class "Default")
      (node (ref "JM3") (pin "49") (pinfunction "49_49") (pintype "passive+no_connect"))
    )
    (net (code "208") (name "unconnected-(JM3-Pad50)") (class "Default")
      (node (ref "JM3") (pin "50") (pinfunction "50_50") (pintype "passive+no_connect"))
    )
    (net (code "209") (name "unconnected-(JM3-Pad51)") (class "Default")
      (node (ref "JM3") (pin "51") (pinfunction "51_51") (pintype "passive+no_connect"))
    )
    (net (code "210") (name "unconnected-(JM3-Pad52)") (class "Default")
      (node (ref "JM3") (pin "52") (pinfunction "52_52") (pintype "passive+no_connect"))
    )
    (net (code "211") (name "unconnected-(JM3-Pad53)") (class "Default")
      (node (ref "JM3") (pin "53") (pinfunction "53_53") (pintype "passive+no_connect"))
    )
    (net (code "212") (name "unconnected-(JM3-Pad54)") (class "Default")
      (node (ref "JM3") (pin "54") (pinfunction "54_54") (pintype "passive+no_connect"))
    )
    (net (code "213") (name "unconnected-(JM3-Pad55)") (class "Default")
      (node (ref "JM3") (pin "55") (pinfunction "55_55") (pintype "passive+no_connect"))
    )
    (net (code "214") (name "unconnected-(JM3-Pad56)") (class "Default")
      (node (ref "JM3") (pin "56") (pinfunction "56_56") (pintype "passive+no_connect"))
    )
    (net (code "215") (name "unconnected-(JM3-Pad57)") (class "Default")
      (node (ref "JM3") (pin "57") (pinfunction "57_57") (pintype "passive+no_connect"))
    )
    (net (code "216") (name "unconnected-(JM3-Pad58)") (class "Default")
      (node (ref "JM3") (pin "58") (pinfunction "58_58") (pintype "passive+no_connect"))
    )
    (net (code "217") (name "unconnected-(JM3-Pad60)") (class "Default")
      (node (ref "JM3") (pin "60") (pinfunction "60_60") (pintype "passive+no_connect"))
    )
  )
)
